# SensorBoard.net
KiCad netlist of a schematic drawn in EAGLE
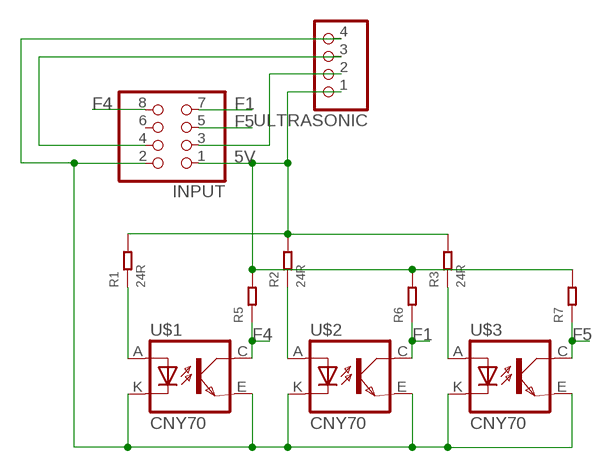
[diagram p0: schematic, sheet 1]

(export (version "E")
  (design (tool "Eeschema 10.0.6"))
  (components
    (comp (ref "INPUT")
      (value "PINHD-2X4")
      (footprint "eagle-import:2X04")
      (libsource (lib "eagle-import") (part "PINHD-2X4"))
    )
    (comp (ref "R1")
      (value "24R")
      (footprint "eagle-import:PR-D2.3XL6.5MM")
      (fields (field (name "MPN") "FHCFR-1/4W-000J"))
      (libsource (lib "eagle-import") (part "DIP-RES-0R-5%-1/4W(2P-D2.3XL6.5MM)"))
    )
    (comp (ref "R2")
      (value "24R")
      (footprint "eagle-import:PR-D2.3XL6.5MM")
      (fields (field (name "MPN") "FHCFR-1/4W-000J"))
      (libsource (lib "eagle-import") (part "DIP-RES-0R-5%-1/4W(2P-D2.3XL6.5MM)"))
    )
    (comp (ref "R3")
      (value "24R")
      (footprint "eagle-import:PR-D2.3XL6.5MM")
      (fields (field (name "MPN") "FHCFR-1/4W-000J"))
      (libsource (lib "eagle-import") (part "DIP-RES-0R-5%-1/4W(2P-D2.3XL6.5MM)"))
    )
    (comp (ref "R5")
      (value "DIP-RES-0R-5%-1/4W(2P-D2.3XL6.5MM)")
      (footprint "eagle-import:PR-D2.3XL6.5MM")
      (fields (field (name "MPN") "FHCFR-1/4W-000J"))
      (libsource (lib "eagle-import") (part "DIP-RES-0R-5%-1/4W(2P-D2.3XL6.5MM)"))
    )
    (comp (ref "R6")
      (value "DIP-RES-0R-5%-1/4W(2P-D2.3XL6.5MM)")
      (footprint "eagle-import:PR-D2.3XL6.5MM")
      (fields (field (name "MPN") "FHCFR-1/4W-000J"))
      (libsource (lib "eagle-import") (part "DIP-RES-0R-5%-1/4W(2P-D2.3XL6.5MM)"))
    )
    (comp (ref "R7")
      (value "DIP-RES-0R-5%-1/4W(2P-D2.3XL6.5MM)")
      (footprint "eagle-import:PR-D2.3XL6.5MM")
      (fields (field (name "MPN") "FHCFR-1/4W-000J"))
      (libsource (lib "eagle-import") (part "DIP-RES-0R-5%-1/4W(2P-D2.3XL6.5MM)"))
    )
    (comp (ref "U$1")
      (value "CNY70")
      (footprint "eagle-import:4")
      (libsource (lib "eagle-import") (part "CNY70"))
    )
    (comp (ref "U$2")
      (value "CNY70")
      (footprint "eagle-import:4")
      (libsource (lib "eagle-import") (part "CNY70"))
    )
    (comp (ref "U$3")
      (value "CNY70")
      (footprint "eagle-import:4")
      (libsource (lib "eagle-import") (part "CNY70"))
    )
    (comp (ref "ULTRASONIC")
      (value "PINHD-1X4")
      (footprint "eagle-import:1X04")
      (libsource (lib "eagle-import") (part "PINHD-1X4"))
    )
  )
  (nets
    (net (code "1") (name "/5V") (class "Default")
      (node (ref "INPUT") (pin "1") (pinfunction "1_1") (pintype "passive"))
      (node (ref "R1") (pin "2") (pinfunction "2_2") (pintype "passive"))
      (node (ref "R2") (pin "2") (pinfunction "2_2") (pintype "passive"))
      (node (ref "R3") (pin "2") (pinfunction "2_2") (pintype "passive"))
      (node (ref "R5") (pin "2") (pinfunction "2_2") (pintype "passive"))
      (node (ref "R6") (pin "2") (pinfunction "2_2") (pintype "passive"))
      (node (ref "R7") (pin "2") (pinfunction "2_2") (pintype "passive"))
      (node (ref "ULTRASONIC") (pin "1") (pinfunction "1_1") (pintype "passive"))
    )
    (net (code "2") (name "/F1") (class "Default")
      (node (ref "INPUT") (pin "7") (pinfunction "7_7") (pintype "passive"))
      (node (ref "R6") (pin "1") (pinfunction "1_1") (pintype "passive"))
      (node (ref "U$2") (pin "C") (pinfunction "COL_C") (pintype "passive"))
    )
    (net (code "3") (name "/F4") (class "Default")
      (node (ref "INPUT") (pin "8") (pinfunction "8_8") (pintype "passive"))
      (node (ref "R5") (pin "1") (pinfunction "1_1") (pintype "passive"))
      (node (ref "U$1") (pin "C") (pinfunction "COL_C") (pintype "passive"))
    )
    (net (code "4") (name "/F5") (class "Default")
      (node (ref "INPUT") (pin "5") (pinfunction "5_5") (pintype "passive"))
      (node (ref "R7") (pin "1") (pinfunction "1_1") (pintype "passive"))
      (node (ref "U$3") (pin "C") (pinfunction "COL_C") (pintype "passive"))
    )
    (net (code "5") (name "Net-(INPUT-Pad3)") (class "Default")
      (node (ref "INPUT") (pin "3") (pinfunction "3_3") (pintype "passive"))
      (node (ref "ULTRASONIC") (pin "2") (pinfunction "2_2") (pintype "passive"))
    )
    (net (code "6") (name "Net-(INPUT-Pad4)") (class "Default")
      (node (ref "INPUT") (pin "4") (pinfunction "4_4") (pintype "passive"))
      (node (ref "ULTRASONIC") (pin "3") (pinfunction "3_3") (pintype "passive"))
    )
    (net (code "7") (name "Net-(R1-Pad1)") (class "Default")
      (node (ref "R1") (pin "1") (pinfunction "1_1") (pintype "passive"))
      (node (ref "U$1") (pin "A") (pinfunction "A_A") (pintype "passive"))
    )
    (net (code "8") (name "Net-(R2-Pad1)") (class "Default")
      (node (ref "R2") (pin "1") (pinfunction "1_1") (pintype "passive"))
      (node (ref "U$2") (pin "A") (pinfunction "A_A") (pintype "passive"))
    )
    (net (code "9") (name "Net-(R3-Pad1)") (class "Default")
      (node (ref "R3") (pin "1") (pinfunction "1_1") (pintype "passive"))
      (node (ref "U$3") (pin "A") (pinfunction "A_A") (pintype "passive"))
    )
    (net (code "10") (name "Net-(U$1-C)") (class "Default")
      (node (ref "INPUT") (pin "2") (pinfunction "2_2") (pintype "passive"))
      (node (ref "U$1") (pin "E") (pinfunction "EMI_E") (pintype "passive"))
      (node (ref "U$1") (pin "K") (pinfunction "C_K") (pintype "passive"))
      (node (ref "U$2") (pin "E") (pinfunction "EMI_E") (pintype "passive"))
      (node (ref "U$2") (pin "K") (pinfunction "C_K") (pintype "passive"))
      (node (ref "U$3") (pin "E") (pinfunction "EMI_E") (pintype "passive"))
      (node (ref "U$3") (pin "K") (pinfunction "C_K") (pintype "passive"))
      (node (ref "ULTRASONIC") (pin "4") (pinfunction "4_4") (pintype "passive"))
    )
    (net (code "11") (name "unconnected-(INPUT-Pad6)") (class "Default")
      (node (ref "INPUT") (pin "6") (pinfunction "6_6") (pintype "passive"))
    )
  )
)
